# tick-display-mk-3.net
KiCad netlist of a schematic drawn in EAGLE
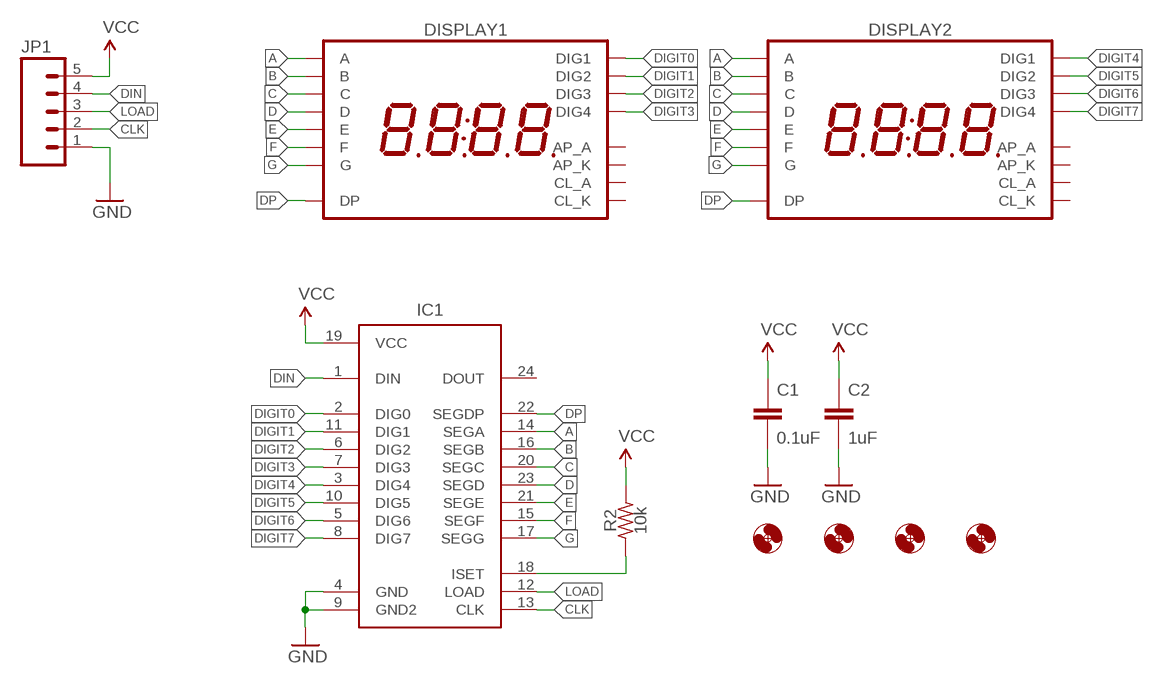
[diagram p0: schematic, sheet 1]

(export (version "E")
  (design (tool "Eeschema 10.0.6"))
  (components
    (comp (ref "C1")
      (value "0.1uF")
      (footprint "eagle-import:C0805")
      (libsource (lib "eagle-import") (part "CAPACITOR-CERAMICC0805"))
    )
    (comp (ref "C2")
      (value "1uF")
      (footprint "eagle-import:C0805")
      (libsource (lib "eagle-import") (part "CAPACITOR-CERAMICC0805"))
    )
    (comp (ref "DISPLAY1")
      (value "7SEG_4DIGIT_10MM")
      (footprint "eagle-import:7SEG_4DIG_10MM")
      (libsource (lib "eagle-import") (part "7SEG_4DIGIT_10MM"))
    )
    (comp (ref "DISPLAY2")
      (value "7SEG_4DIGIT_10MM")
      (footprint "eagle-import:7SEG_4DIG_10MM")
      (libsource (lib "eagle-import") (part "7SEG_4DIGIT_10MM"))
    )
    (comp (ref "H1")
      (value "HOLE#2")
      (footprint "eagle-import:HOLE-#2")
      (libsource (lib "eagle-import") (part "HOLE#2"))
    )
    (comp (ref "H2")
      (value "HOLE#2")
      (footprint "eagle-import:HOLE-#2")
      (libsource (lib "eagle-import") (part "HOLE#2"))
    )
    (comp (ref "H3")
      (value "HOLE#2")
      (footprint "eagle-import:HOLE-#2")
      (libsource (lib "eagle-import") (part "HOLE#2"))
    )
    (comp (ref "H4")
      (value "HOLE#2")
      (footprint "eagle-import:HOLE-#2")
      (libsource (lib "eagle-import") (part "HOLE#2"))
    )
    (comp (ref "IC1")
      (value "MAX7219CWG")
      (footprint "eagle-import:SO24W")
      (libsource (lib "eagle-import") (part "MAX7219SOIC-W"))
    )
    (comp (ref "JP1")
      (value "M05JST-PH-RA-PTH")
      (footprint "eagle-import:JST-5-PH-RA-PTH")
      (libsource (lib "eagle-import") (part "M05JST-PH-RA-PTH"))
    )
    (comp (ref "R2")
      (value "10k")
      (footprint "eagle-import:R0805")
      (libsource (lib "eagle-import") (part "RESISTORR0805"))
    )
  )
  (nets
    (net (code "1") (name "A") (class "Default")
      (node (ref "DISPLAY1") (pin "14") (pinfunction "A_14") (pintype "passive"))
      (node (ref "DISPLAY2") (pin "14") (pinfunction "A_14") (pintype "passive"))
      (node (ref "IC1") (pin "14") (pinfunction "SEGA_14") (pintype "bidirectional"))
    )
    (net (code "2") (name "B") (class "Default")
      (node (ref "DISPLAY1") (pin "16") (pinfunction "B_16") (pintype "passive"))
      (node (ref "DISPLAY2") (pin "16") (pinfunction "B_16") (pintype "passive"))
      (node (ref "IC1") (pin "16") (pinfunction "SEGB_16") (pintype "bidirectional"))
    )
    (net (code "3") (name "C") (class "Default")
      (node (ref "DISPLAY1") (pin "13") (pinfunction "C_13") (pintype "passive"))
      (node (ref "DISPLAY2") (pin "13") (pinfunction "C_13") (pintype "passive"))
      (node (ref "IC1") (pin "20") (pinfunction "SEGC_20") (pintype "bidirectional"))
    )
    (net (code "4") (name "CLK") (class "Default")
      (node (ref "IC1") (pin "13") (pinfunction "CLK_13") (pintype "bidirectional"))
      (node (ref "JP1") (pin "2") (pinfunction "2_2") (pintype "passive"))
    )
    (net (code "5") (name "D") (class "Default")
      (node (ref "DISPLAY1") (pin "3") (pinfunction "D_3") (pintype "passive"))
      (node (ref "DISPLAY2") (pin "3") (pinfunction "D_3") (pintype "passive"))
      (node (ref "IC1") (pin "23") (pinfunction "SEGD_23") (pintype "bidirectional"))
    )
    (net (code "6") (name "DIGIT0") (class "Default")
      (node (ref "DISPLAY1") (pin "1") (pinfunction "DIG1_1") (pintype "passive"))
      (node (ref "IC1") (pin "2") (pinfunction "DIG0_2") (pintype "bidirectional"))
    )
    (net (code "7") (name "DIGIT1") (class "Default")
      (node (ref "DISPLAY1") (pin "2") (pinfunction "DIG2_2") (pintype "passive"))
      (node (ref "IC1") (pin "11") (pinfunction "DIG1_11") (pintype "bidirectional"))
    )
    (net (code "8") (name "DIGIT2") (class "Default")
      (node (ref "DISPLAY1") (pin "6") (pinfunction "DIG3_6") (pintype "passive"))
      (node (ref "IC1") (pin "6") (pinfunction "DIG2_6") (pintype "bidirectional"))
    )
    (net (code "9") (name "DIGIT3") (class "Default")
      (node (ref "DISPLAY1") (pin "8") (pinfunction "DIG4_8") (pintype "passive"))
      (node (ref "IC1") (pin "7") (pinfunction "DIG3_7") (pintype "bidirectional"))
    )
    (net (code "10") (name "DIGIT4") (class "Default")
      (node (ref "DISPLAY2") (pin "1") (pinfunction "DIG1_1") (pintype "passive"))
      (node (ref "IC1") (pin "3") (pinfunction "DIG4_3") (pintype "bidirectional"))
    )
    (net (code "11") (name "DIGIT5") (class "Default")
      (node (ref "DISPLAY2") (pin "2") (pinfunction "DIG2_2") (pintype "passive"))
      (node (ref "IC1") (pin "10") (pinfunction "DIG5_10") (pintype "bidirectional"))
    )
    (net (code "12") (name "DIGIT6") (class "Default")
      (node (ref "DISPLAY2") (pin "6") (pinfunction "DIG3_6") (pintype "passive"))
      (node (ref "IC1") (pin "5") (pinfunction "DIG6_5") (pintype "bidirectional"))
    )
    (net (code "13") (name "DIGIT7") (class "Default")
      (node (ref "DISPLAY2") (pin "8") (pinfunction "DIG4_8") (pintype "passive"))
      (node (ref "IC1") (pin "8") (pinfunction "DIG7_8") (pintype "bidirectional"))
    )
    (net (code "14") (name "DIN") (class "Default")
      (node (ref "IC1") (pin "1") (pinfunction "DIN_1") (pintype "bidirectional"))
      (node (ref "JP1") (pin "4") (pinfunction "4_4") (pintype "passive"))
    )
    (net (code "15") (name "DP") (class "Default")
      (node (ref "DISPLAY1") (pin "7") (pinfunction "DP_7") (pintype "passive"))
      (node (ref "DISPLAY2") (pin "7") (pinfunction "DP_7") (pintype "passive"))
      (node (ref "IC1") (pin "22") (pinfunction "SEGDP_22") (pintype "bidirectional"))
    )
    (net (code "16") (name "E") (class "Default")
      (node (ref "DISPLAY1") (pin "5") (pinfunction "E_5") (pintype "passive"))
      (node (ref "DISPLAY2") (pin "5") (pinfunction "E_5") (pintype "passive"))
      (node (ref "IC1") (pin "21") (pinfunction "SEGE_21") (pintype "bidirectional"))
    )
    (net (code "17") (name "F") (class "Default")
      (node (ref "DISPLAY1") (pin "11") (pinfunction "F_11") (pintype "passive"))
      (node (ref "DISPLAY2") (pin "11") (pinfunction "F_11") (pintype "passive"))
      (node (ref "IC1") (pin "15") (pinfunction "SEGF_15") (pintype "bidirectional"))
    )
    (net (code "18") (name "G") (class "Default")
      (node (ref "DISPLAY1") (pin "15") (pinfunction "G_15") (pintype "passive"))
      (node (ref "DISPLAY2") (pin "15") (pinfunction "G_15") (pintype "passive"))
      (node (ref "IC1") (pin "17") (pinfunction "SEGG_17") (pintype "bidirectional"))
    )
    (net (code "19") (name "GND") (class "Default")
      (node (ref "C1") (pin "2") (pinfunction "2_2") (pintype "passive"))
      (node (ref "C2") (pin "2") (pinfunction "2_2") (pintype "passive"))
      (node (ref "IC1") (pin "4") (pinfunction "GND_4") (pintype "bidirectional"))
      (node (ref "IC1") (pin "9") (pinfunction "GND2_9") (pintype "bidirectional"))
      (node (ref "JP1") (pin "1") (pinfunction "1_1") (pintype "passive"))
    )
    (net (code "20") (name "LOAD") (class "Default")
      (node (ref "IC1") (pin "12") (pinfunction "LOAD_12") (pintype "bidirectional"))
      (node (ref "JP1") (pin "3") (pinfunction "3_3") (pintype "passive"))
    )
    (net (code "21") (name "Net-(IC1-ISET)") (class "Default")
      (node (ref "IC1") (pin "18") (pinfunction "ISET_18") (pintype "bidirectional"))
      (node (ref "R2") (pin "1") (pinfunction "1_1") (pintype "passive"))
    )
    (net (code "22") (name "VCC") (class "Default")
      (node (ref "C1") (pin "1") (pinfunction "1_1") (pintype "passive"))
      (node (ref "C2") (pin "1") (pinfunction "1_1") (pintype "passive"))
      (node (ref "IC1") (pin "19") (pinfunction "VCC_19") (pintype "bidirectional"))
      (node (ref "JP1") (pin "5") (pinfunction "5_5") (pintype "passive"))
      (node (ref "R2") (pin "2") (pinfunction "2_2") (pintype "passive"))
    )
    (net (code "23") (name "unconnected-(DISPLAY1-AP_A-Pad10)") (class "Default")
      (node (ref "DISPLAY1") (pin "10") (pinfunction "AP_A_10") (pintype "bidirectional"))
    )
    (net (code "24") (name "unconnected-(DISPLAY1-AP_K-Pad9)") (class "Default")
      (node (ref "DISPLAY1") (pin "9") (pinfunction "AP_K_9") (pintype "bidirectional"))
    )
    (net (code "25") (name "unconnected-(DISPLAY1-CL_A-Pad4)") (class "Default")
      (node (ref "DISPLAY1") (pin "4") (pinfunction "CL_A_4") (pintype "passive"))
    )
    (net (code "26") (name "unconnected-(DISPLAY1-CL_K-Pad12)") (class "Default")
      (node (ref "DISPLAY1") (pin "12") (pinfunction "CL_K_12") (pintype "passive"))
    )
    (net (code "27") (name "unconnected-(DISPLAY2-AP_A-Pad10)") (class "Default")
      (node (ref "DISPLAY2") (pin "10") (pinfunction "AP_A_10") (pintype "bidirectional"))
    )
    (net (code "28") (name "unconnected-(DISPLAY2-AP_K-Pad9)") (class "Default")
      (node (ref "DISPLAY2") (pin "9") (pinfunction "AP_K_9") (pintype "bidirectional"))
    )
    (net (code "29") (name "unconnected-(DISPLAY2-CL_A-Pad4)") (class "Default")
      (node (ref "DISPLAY2") (pin "4") (pinfunction "CL_A_4") (pintype "passive"))
    )
    (net (code "30") (name "unconnected-(DISPLAY2-CL_K-Pad12)") (class "Default")
      (node (ref "DISPLAY2") (pin "12") (pinfunction "CL_K_12") (pintype "passive"))
    )
    (net (code "31") (name "unconnected-(IC1-DOUT-Pad24)") (class "Default")
      (node (ref "IC1") (pin "24") (pinfunction "DOUT_24") (pintype "bidirectional"))
    )
  )
)
